# MotorBrackets.net
KiCad netlist of a schematic drawn in EAGLE
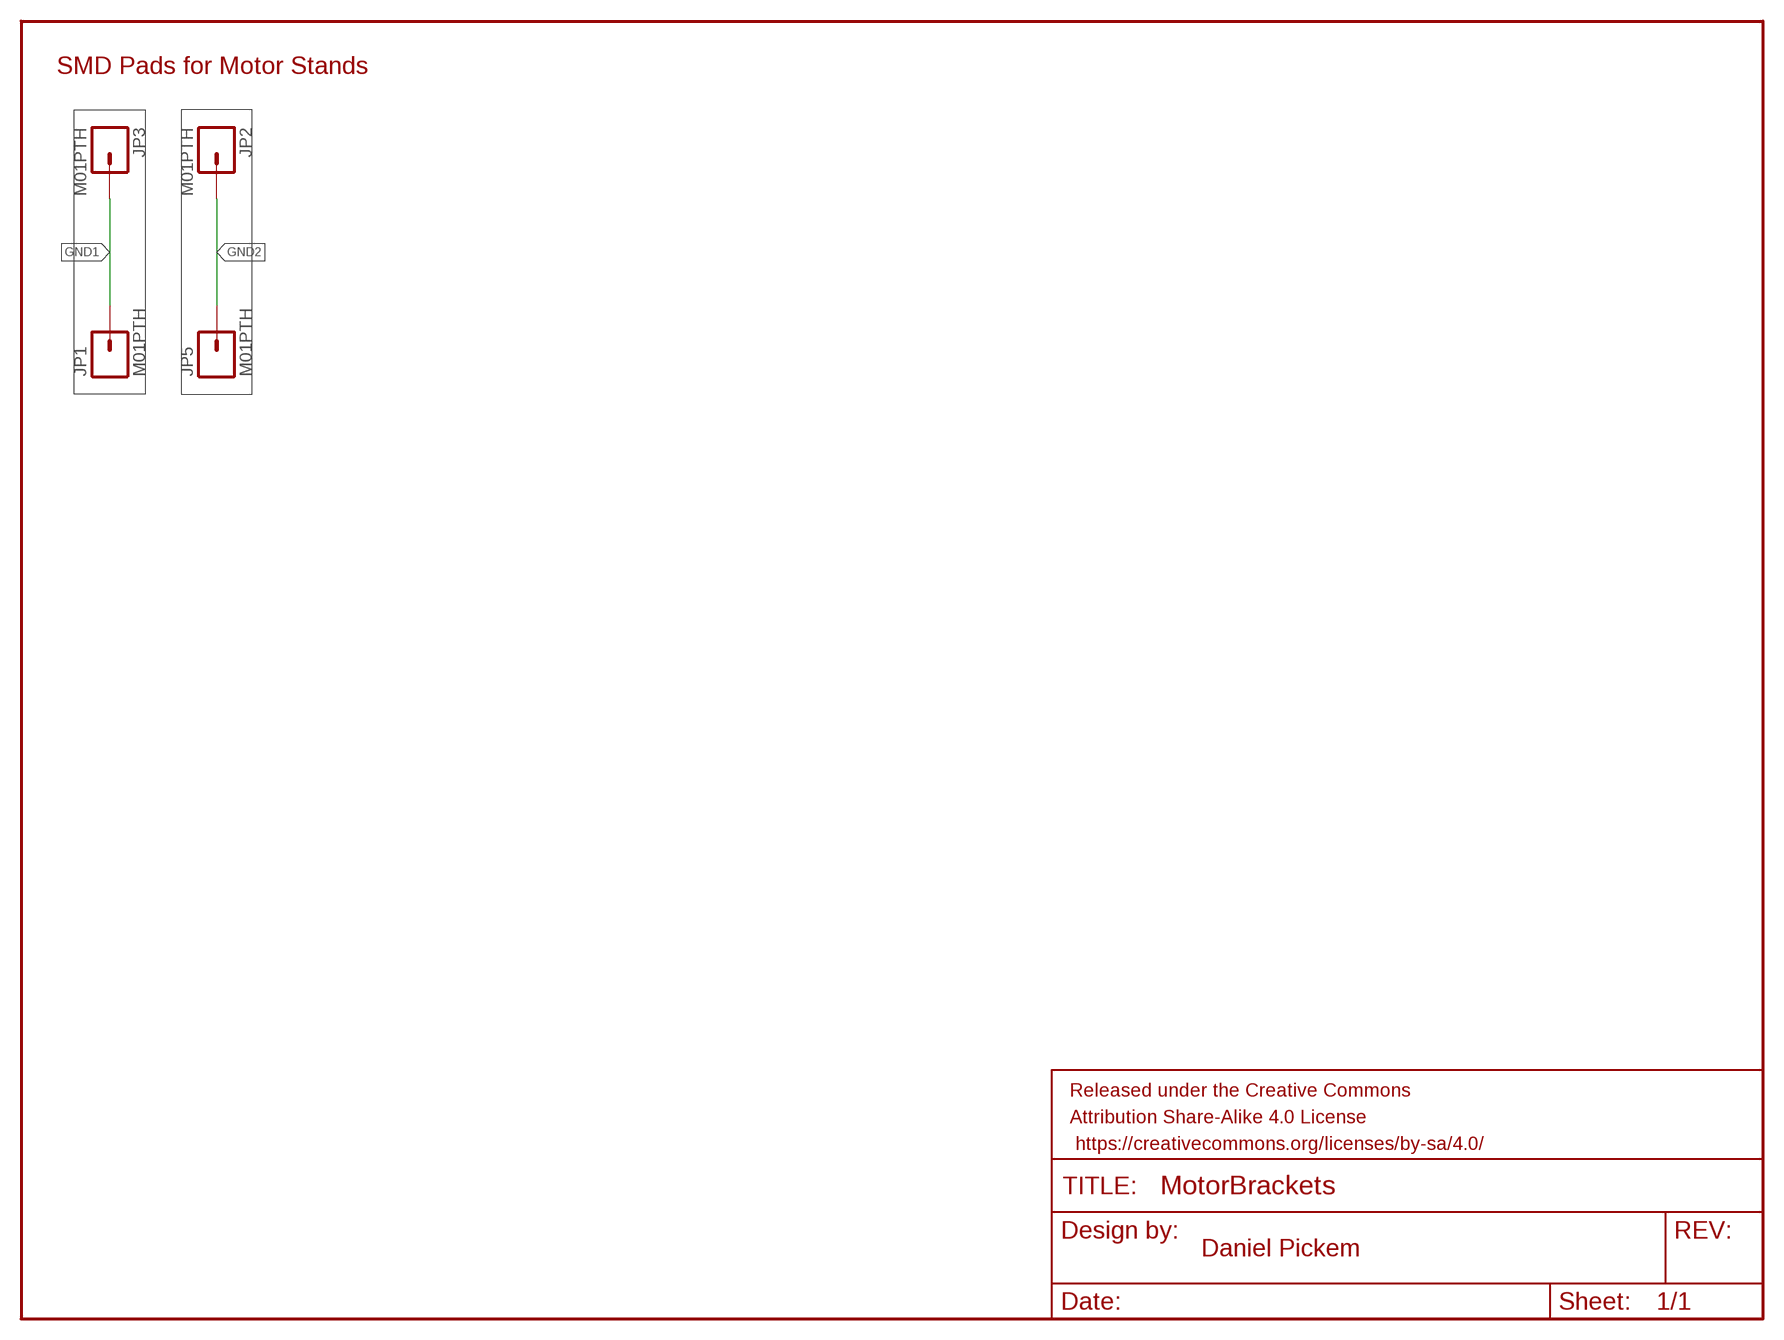
[diagram p0: schematic, sheet 1]

(export (version "E")
  (design (tool "Eeschema 10.0.6"))
  (components
    (comp (ref "FRAME1")
      (value "FRAME-LETTER")
      (footprint "eagle-import:CREATIVE_COMMONS")
      (libsource (lib "eagle-import") (part "FRAME-LETTER"))
    )
    (comp (ref "JP1")
      (value "M01PTH")
      (footprint "eagle-import:1X01")
      (libsource (lib "eagle-import") (part "M01PTH"))
    )
    (comp (ref "JP2")
      (value "M01PTH")
      (footprint "eagle-import:1X01")
      (libsource (lib "eagle-import") (part "M01PTH"))
    )
    (comp (ref "JP3")
      (value "M01PTH")
      (footprint "eagle-import:1X01")
      (libsource (lib "eagle-import") (part "M01PTH"))
    )
    (comp (ref "JP5")
      (value "M01PTH")
      (footprint "eagle-import:1X01")
      (libsource (lib "eagle-import") (part "M01PTH"))
    )
  )
  (nets
    (net (code "1") (name "GND1") (class "Default")
      (node (ref "JP1") (pin "1") (pinfunction "1_1") (pintype "passive"))
      (node (ref "JP3") (pin "1") (pinfunction "1_1") (pintype "passive"))
    )
    (net (code "2") (name "GND2") (class "Default")
      (node (ref "JP2") (pin "1") (pinfunction "1_1") (pintype "passive"))
      (node (ref "JP5") (pin "1") (pinfunction "1_1") (pintype "passive"))
    )
  )
)
